# mainboard.net
KiCad netlist of a schematic drawn in EAGLE
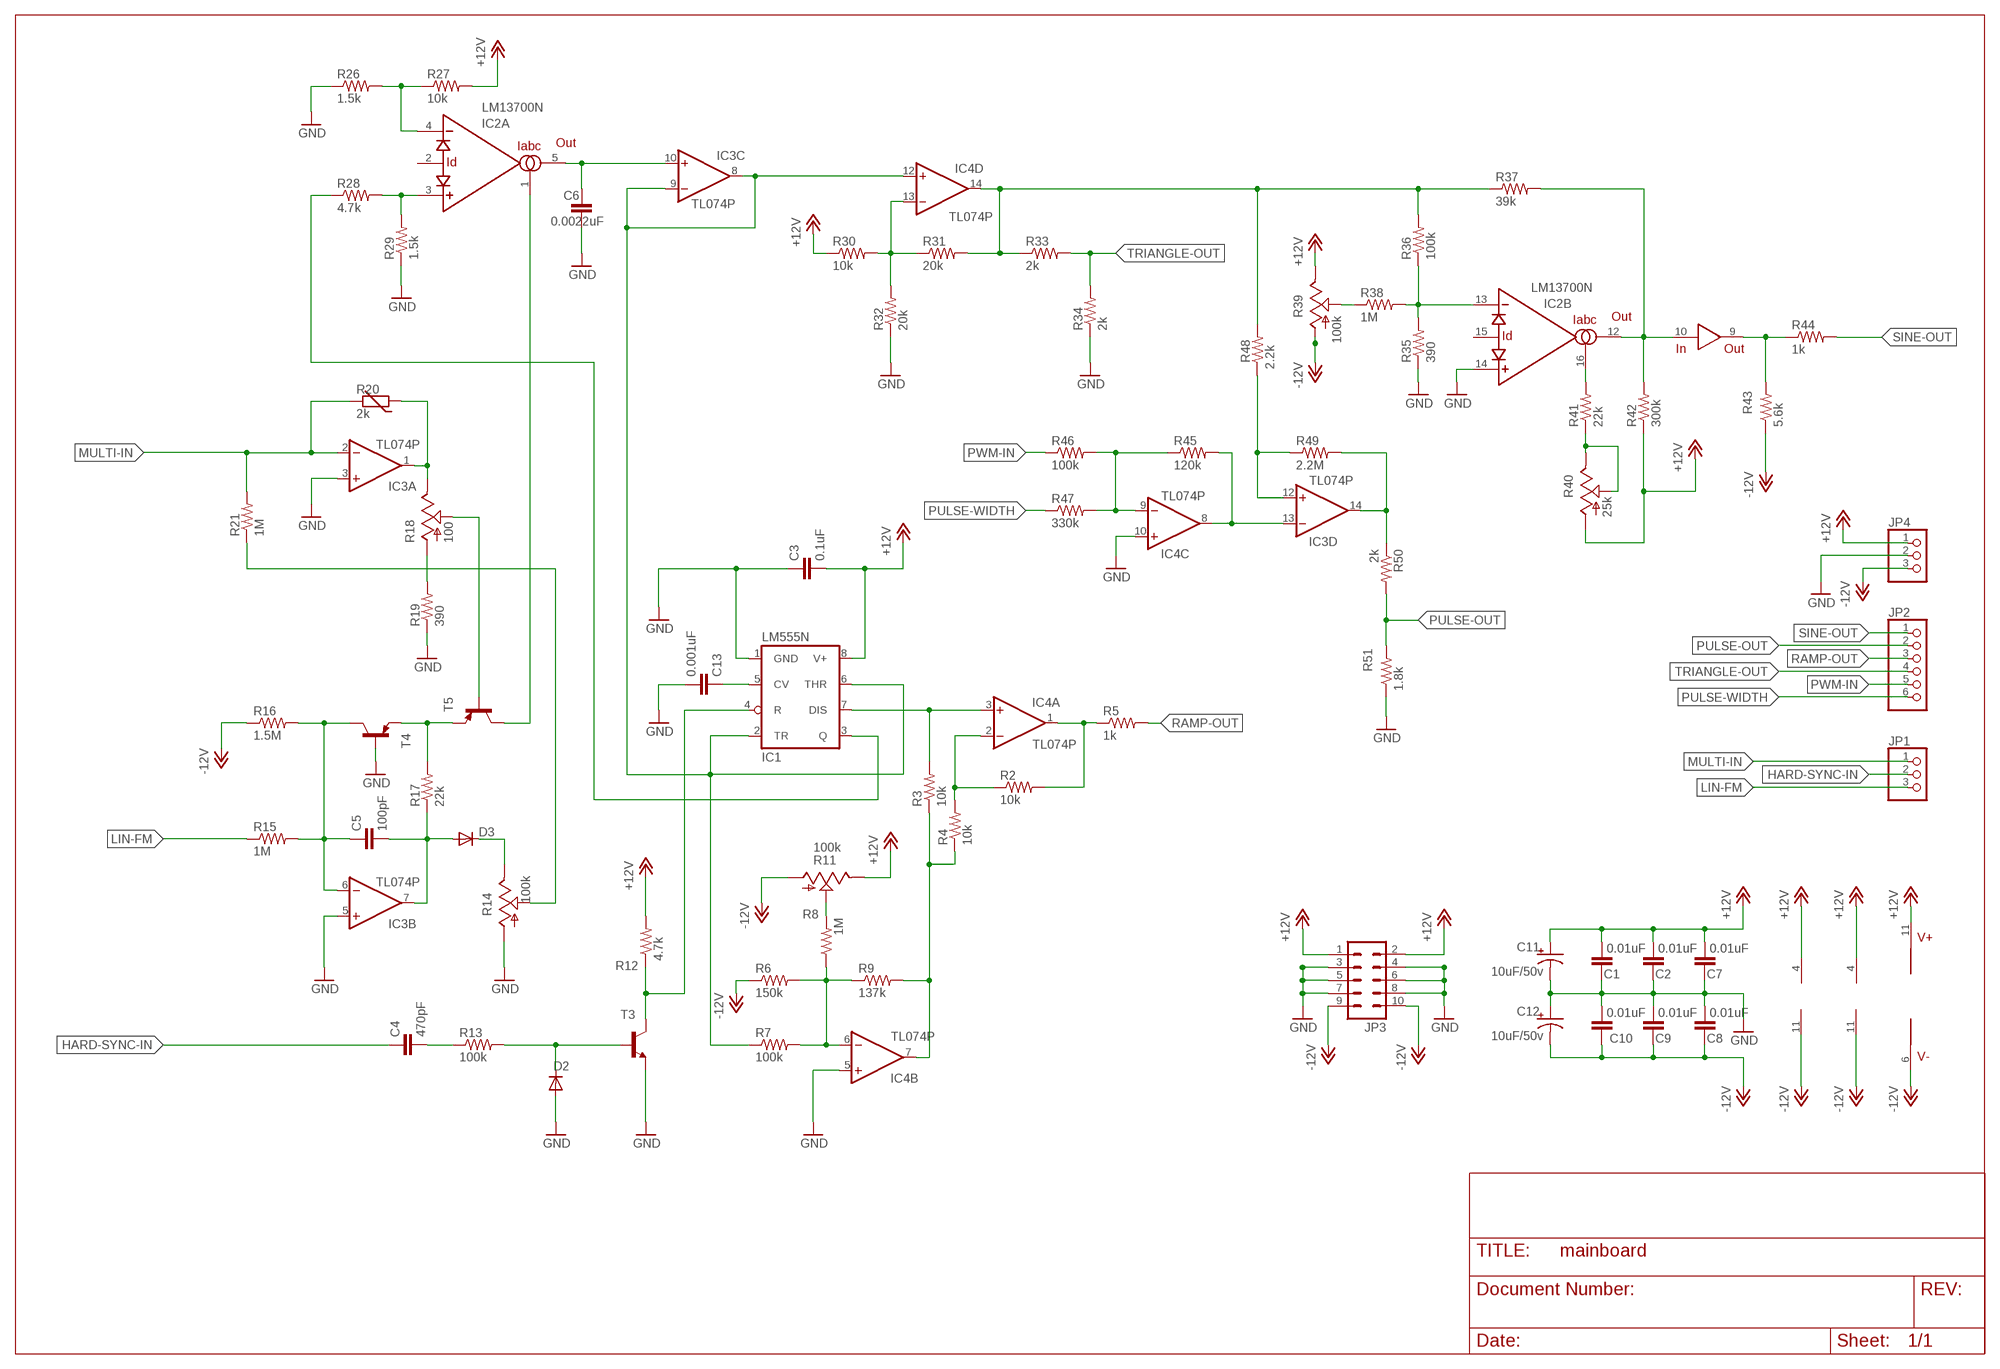
[diagram p0: schematic, sheet 1]

(export (version "E")
  (design (tool "Eeschema 10.0.6"))
  (components
    (comp (ref "C1")
      (value "0.01uF")
      (footprint "eagle-import:C050-024X044")
      (libsource (lib "eagle-import") (part "C-EU050-024X044"))
    )
    (comp (ref "C2")
      (value "0.01uF")
      (footprint "eagle-import:C050-024X044")
      (libsource (lib "eagle-import") (part "C-EU050-024X044"))
    )
    (comp (ref "C3")
      (value "0.1uF")
      (footprint "eagle-import:C050-024X044")
      (libsource (lib "eagle-import") (part "C-EU050-024X044"))
    )
    (comp (ref "C4")
      (value "470pF")
      (footprint "eagle-import:C050-024X044")
      (libsource (lib "eagle-import") (part "C-EU050-024X044"))
    )
    (comp (ref "C5")
      (value "100pF")
      (footprint "eagle-import:C050-024X044")
      (libsource (lib "eagle-import") (part "C-EU050-024X044"))
    )
    (comp (ref "C6")
      (value "0.0022uF")
      (footprint "eagle-import:C050-025X075")
      (libsource (lib "eagle-import") (part "C-EU050-025X075"))
    )
    (comp (ref "C7")
      (value "0.01uF")
      (footprint "eagle-import:C050-024X044")
      (libsource (lib "eagle-import") (part "C-EU050-024X044"))
    )
    (comp (ref "C8")
      (value "0.01uF")
      (footprint "eagle-import:C050-024X044")
      (libsource (lib "eagle-import") (part "C-EU050-024X044"))
    )
    (comp (ref "C9")
      (value "0.01uF")
      (footprint "eagle-import:C050-024X044")
      (libsource (lib "eagle-import") (part "C-EU050-024X044"))
    )
    (comp (ref "C10")
      (value "0.01uF")
      (footprint "eagle-import:C050-024X044")
      (libsource (lib "eagle-import") (part "C-EU050-024X044"))
    )
    (comp (ref "C11")
      (value "10uF/50v")
      (footprint "eagle-import:E2,5-6")
      (libsource (lib "eagle-import") (part "CPOL-USE2.5-6"))
    )
    (comp (ref "C12")
      (value "10uF/50v")
      (footprint "eagle-import:E2,5-6")
      (libsource (lib "eagle-import") (part "CPOL-USE2.5-6"))
    )
    (comp (ref "C13")
      (value "0.001uF")
      (footprint "eagle-import:C050-024X044")
      (libsource (lib "eagle-import") (part "C-EU050-024X044"))
    )
    (comp (ref "D2")
      (value "1N4148DO35-7")
      (footprint "eagle-import:DO35-7")
      (libsource (lib "eagle-import") (part "1N4148DO35-7"))
    )
    (comp (ref "D3")
      (value "1N4148DO35-7")
      (footprint "eagle-import:DO35-7")
      (libsource (lib "eagle-import") (part "1N4148DO35-7"))
    )
    (comp (ref "IC1")
      (value "LM555N")
      (footprint "eagle-import:DIL08")
      (libsource (lib "eagle-import") (part "555NLM"))
    )
    (comp (ref "IC2")
      (value "LM13700N")
      (footprint "eagle-import:DIL16")
      (libsource (lib "eagle-import") (part "LM13700N"))
    )
    (comp (ref "IC3")
      (value "TL074P")
      (footprint "eagle-import:DIL14")
      (libsource (lib "eagle-import") (part "TL074P"))
    )
    (comp (ref "IC4")
      (value "TL074P")
      (footprint "eagle-import:DIL14")
      (libsource (lib "eagle-import") (part "TL074P"))
    )
    (comp (ref "JP1")
      (value "PINHD-1X3")
      (footprint "eagle-import:1X03")
      (libsource (lib "eagle-import") (part "PINHD-1X3"))
    )
    (comp (ref "JP2")
      (value "PINHD-1X6")
      (footprint "eagle-import:1X06")
      (libsource (lib "eagle-import") (part "PINHD-1X6"))
    )
    (comp (ref "JP3")
      (value "ML10")
      (footprint "eagle-import:ML10")
      (libsource (lib "eagle-import") (part "ML10"))
    )
    (comp (ref "JP4")
      (value "PINHD-1X3")
      (footprint "eagle-import:1X03")
      (libsource (lib "eagle-import") (part "PINHD-1X3"))
    )
    (comp (ref "R2")
      (value "10k")
      (footprint "eagle-import:0204_7")
      (libsource (lib "eagle-import") (part "R-US_0204/7"))
    )
    (comp (ref "R3")
      (value "10k")
      (footprint "eagle-import:0204_7")
      (libsource (lib "eagle-import") (part "R-US_0204/7"))
    )
    (comp (ref "R4")
      (value "10k")
      (footprint "eagle-import:0204_7")
      (libsource (lib "eagle-import") (part "R-US_0204/7"))
    )
    (comp (ref "R5")
      (value "1k")
      (footprint "eagle-import:0204_7")
      (libsource (lib "eagle-import") (part "R-US_0204/7"))
    )
    (comp (ref "R6")
      (value "150k")
      (footprint "eagle-import:0204_7")
      (libsource (lib "eagle-import") (part "R-US_0204/7"))
    )
    (comp (ref "R7")
      (value "100k")
      (footprint "eagle-import:0204_7")
      (libsource (lib "eagle-import") (part "R-US_0204/7"))
    )
    (comp (ref "R8")
      (value "1M")
      (footprint "eagle-import:0204_7")
      (libsource (lib "eagle-import") (part "R-US_0204/7"))
    )
    (comp (ref "R9")
      (value "137k")
      (footprint "eagle-import:0204_7")
      (libsource (lib "eagle-import") (part "R-US_0204/7"))
    )
    (comp (ref "R11")
      (value "100k")
      (footprint "eagle-import:RJ9W")
      (libsource (lib "eagle-import") (part "TRIM_US-RJ9W"))
    )
    (comp (ref "R12")
      (value "4.7k")
      (footprint "eagle-import:0204_7")
      (libsource (lib "eagle-import") (part "R-US_0204/7"))
    )
    (comp (ref "R13")
      (value "100k")
      (footprint "eagle-import:0204_7")
      (libsource (lib "eagle-import") (part "R-US_0204/7"))
    )
    (comp (ref "R14")
      (value "100k")
      (footprint "eagle-import:RJ9W")
      (libsource (lib "eagle-import") (part "TRIM_US-RJ9W"))
    )
    (comp (ref "R15")
      (value "1M")
      (footprint "eagle-import:0204_7")
      (libsource (lib "eagle-import") (part "R-US_0204/7"))
    )
    (comp (ref "R16")
      (value "1.5M")
      (footprint "eagle-import:0204_7")
      (libsource (lib "eagle-import") (part "R-US_0204/7"))
    )
    (comp (ref "R17")
      (value "22k")
      (footprint "eagle-import:0204_7")
      (libsource (lib "eagle-import") (part "R-US_0204/7"))
    )
    (comp (ref "R18")
      (value "100")
      (footprint "eagle-import:RJ9W")
      (libsource (lib "eagle-import") (part "TRIM_US-RJ9W"))
    )
    (comp (ref "R19")
      (value "390")
      (footprint "eagle-import:0204_7")
      (libsource (lib "eagle-import") (part "R-US_0204/7"))
    )
    (comp (ref "R20")
      (value "2k")
      (footprint "eagle-import:R-5")
      (libsource (lib "eagle-import") (part "THERMISTOR-5"))
    )
    (comp (ref "R21")
      (value "1M")
      (footprint "eagle-import:0204_7")
      (libsource (lib "eagle-import") (part "R-US_0204/7"))
    )
    (comp (ref "R26")
      (value "1.5k")
      (footprint "eagle-import:0204_7")
      (libsource (lib "eagle-import") (part "R-US_0204/7"))
    )
    (comp (ref "R27")
      (value "10k")
      (footprint "eagle-import:0204_7")
      (libsource (lib "eagle-import") (part "R-US_0204/7"))
    )
    (comp (ref "R28")
      (value "4.7k")
      (footprint "eagle-import:0204_7")
      (libsource (lib "eagle-import") (part "R-US_0204/7"))
    )
    (comp (ref "R29")
      (value "1.5k")
      (footprint "eagle-import:0204_7")
      (libsource (lib "eagle-import") (part "R-US_0204/7"))
    )
    (comp (ref "R30")
      (value "10k")
      (footprint "eagle-import:0204_7")
      (libsource (lib "eagle-import") (part "R-US_0204/7"))
    )
    (comp (ref "R31")
      (value "20k")
      (footprint "eagle-import:0204_7")
      (libsource (lib "eagle-import") (part "R-US_0204/7"))
    )
    (comp (ref "R32")
      (value "20k")
      (footprint "eagle-import:0204_7")
      (libsource (lib "eagle-import") (part "R-US_0204/7"))
    )
    (comp (ref "R33")
      (value "2k")
      (footprint "eagle-import:0204_7")
      (libsource (lib "eagle-import") (part "R-US_0204/7"))
    )
    (comp (ref "R34")
      (value "2k")
      (footprint "eagle-import:0204_7")
      (libsource (lib "eagle-import") (part "R-US_0204/7"))
    )
    (comp (ref "R35")
      (value "390")
      (footprint "eagle-import:0204_7")
      (libsource (lib "eagle-import") (part "R-US_0204/7"))
    )
    (comp (ref "R36")
      (value "100k")
      (footprint "eagle-import:0204_7")
      (libsource (lib "eagle-import") (part "R-US_0204/7"))
    )
    (comp (ref "R37")
      (value "39k")
      (footprint "eagle-import:0204_7")
      (libsource (lib "eagle-import") (part "R-US_0204/7"))
    )
    (comp (ref "R38")
      (value "1M")
      (footprint "eagle-import:0204_7")
      (libsource (lib "eagle-import") (part "R-US_0204/7"))
    )
    (comp (ref "R39")
      (value "100k")
      (footprint "eagle-import:RJ9W")
      (libsource (lib "eagle-import") (part "TRIM_US-RJ9W"))
    )
    (comp (ref "R40")
      (value "25k")
      (footprint "eagle-import:RJ9W")
      (libsource (lib "eagle-import") (part "TRIM_US-RJ9W"))
    )
    (comp (ref "R41")
      (value "22k")
      (footprint "eagle-import:0204_7")
      (libsource (lib "eagle-import") (part "R-US_0204/7"))
    )
    (comp (ref "R42")
      (value "300k")
      (footprint "eagle-import:0204_7")
      (libsource (lib "eagle-import") (part "R-US_0204/7"))
    )
    (comp (ref "R43")
      (value "5.6k")
      (footprint "eagle-import:0204_7")
      (libsource (lib "eagle-import") (part "R-US_0204/7"))
    )
    (comp (ref "R44")
      (value "1k")
      (footprint "eagle-import:0204_7")
      (libsource (lib "eagle-import") (part "R-US_0204/7"))
    )
    (comp (ref "R45")
      (value "120k")
      (footprint "eagle-import:0204_7")
      (libsource (lib "eagle-import") (part "R-US_0204/7"))
    )
    (comp (ref "R46")
      (value "100k")
      (footprint "eagle-import:0204_7")
      (libsource (lib "eagle-import") (part "R-US_0204/7"))
    )
    (comp (ref "R47")
      (value "330k")
      (footprint "eagle-import:0204_7")
      (libsource (lib "eagle-import") (part "R-US_0204/7"))
    )
    (comp (ref "R48")
      (value "2.2k")
      (footprint "eagle-import:0204_7")
      (libsource (lib "eagle-import") (part "R-US_0204/7"))
    )
    (comp (ref "R49")
      (value "2.2M")
      (footprint "eagle-import:0204_7")
      (libsource (lib "eagle-import") (part "R-US_0204/7"))
    )
    (comp (ref "R50")
      (value "2k")
      (footprint "eagle-import:0204_7")
      (libsource (lib "eagle-import") (part "R-US_0204/7"))
    )
    (comp (ref "R51")
      (value "1.8k")
      (footprint "eagle-import:0204_7")
      (libsource (lib "eagle-import") (part "R-US_0204/7"))
    )
    (comp (ref "T3")
      (value "2N3904-NPN-TO92-EBC")
      (footprint "eagle-import:TO92-EBC")
      (libsource (lib "eagle-import") (part "-NPN-TO92-EBC2N3904"))
    )
    (comp (ref "T4")
      (value "2N3906-PNP-TO92-EBC")
      (footprint "eagle-import:TO92-EBC")
      (libsource (lib "eagle-import") (part "-PNP-TO92-EBC2N3906"))
    )
    (comp (ref "T5")
      (value "2N3906-PNP-TO92-EBC")
      (footprint "eagle-import:TO92-EBC")
      (libsource (lib "eagle-import") (part "-PNP-TO92-EBC2N3906"))
    )
  )
  (nets
    (net (code "1") (name "+12V") (class "Default")
      (node (ref "C1") (pin "2") (pinfunction "2_2") (pintype "passive"))
      (node (ref "C11") (pin "+") (pinfunction "+_+") (pintype "passive"))
      (node (ref "C2") (pin "2") (pinfunction "2_2") (pintype "passive"))
      (node (ref "C3") (pin "2") (pinfunction "2_2") (pintype "passive"))
      (node (ref "C7") (pin "2") (pinfunction "2_2") (pintype "passive"))
      (node (ref "IC1") (pin "8") (pinfunction "V+_8") (pintype "power_in"))
      (node (ref "IC2") (pin "11") (pinfunction "V+_11") (pintype "bidirectional"))
      (node (ref "IC3") (pin "4") (pinfunction "V+_4") (pintype "power_in"))
      (node (ref "IC4") (pin "4") (pinfunction "V+_4") (pintype "power_in"))
      (node (ref "JP3") (pin "1") (pinfunction "1_1") (pintype "passive"))
      (node (ref "JP3") (pin "2") (pinfunction "2_2") (pintype "passive"))
      (node (ref "JP4") (pin "1") (pinfunction "1_1") (pintype "passive"))
      (node (ref "R11") (pin "E") (pinfunction "E_E") (pintype "passive"))
      (node (ref "R12") (pin "2") (pinfunction "2_2") (pintype "passive"))
      (node (ref "R27") (pin "2") (pinfunction "2_2") (pintype "passive"))
      (node (ref "R30") (pin "1") (pinfunction "1_1") (pintype "passive"))
      (node (ref "R39") (pin "E") (pinfunction "E_E") (pintype "passive"))
      (node (ref "R40") (pin "A") (pinfunction "A_A") (pintype "passive"))
      (node (ref "R42") (pin "1") (pinfunction "1_1") (pintype "passive"))
    )
    (net (code "2") (name "-12V") (class "Default")
      (node (ref "C10") (pin "1") (pinfunction "1_1") (pintype "passive"))
      (node (ref "C12") (pin "-") (pinfunction "-_-") (pintype "passive"))
      (node (ref "C8") (pin "1") (pinfunction "1_1") (pintype "passive"))
      (node (ref "C9") (pin "1") (pinfunction "1_1") (pintype "passive"))
      (node (ref "IC2") (pin "6") (pinfunction "V-_6") (pintype "bidirectional"))
      (node (ref "IC3") (pin "11") (pinfunction "V-_11") (pintype "power_in"))
      (node (ref "IC4") (pin "11") (pinfunction "V-_11") (pintype "power_in"))
      (node (ref "JP3") (pin "10") (pinfunction "10_10") (pintype "passive"))
      (node (ref "JP3") (pin "9") (pinfunction "9_9") (pintype "passive"))
      (node (ref "JP4") (pin "3") (pinfunction "3_3") (pintype "passive"))
      (node (ref "R11") (pin "A") (pinfunction "A_A") (pintype "passive"))
      (node (ref "R16") (pin "1") (pinfunction "1_1") (pintype "passive"))
      (node (ref "R39") (pin "A") (pinfunction "A_A") (pintype "passive"))
      (node (ref "R43") (pin "1") (pinfunction "1_1") (pintype "passive"))
      (node (ref "R6") (pin "1") (pinfunction "1_1") (pintype "passive"))
    )
    (net (code "3") (name "GND") (class "Default")
      (node (ref "C1") (pin "1") (pinfunction "1_1") (pintype "passive"))
      (node (ref "C10") (pin "2") (pinfunction "2_2") (pintype "passive"))
      (node (ref "C11") (pin "-") (pinfunction "-_-") (pintype "passive"))
      (node (ref "C12") (pin "+") (pinfunction "+_+") (pintype "passive"))
      (node (ref "C13") (pin "1") (pinfunction "1_1") (pintype "passive"))
      (node (ref "C2") (pin "1") (pinfunction "1_1") (pintype "passive"))
      (node (ref "C3") (pin "1") (pinfunction "1_1") (pintype "passive"))
      (node (ref "C6") (pin "2") (pinfunction "2_2") (pintype "passive"))
      (node (ref "C7") (pin "1") (pinfunction "1_1") (pintype "passive"))
      (node (ref "C8") (pin "2") (pinfunction "2_2") (pintype "passive"))
      (node (ref "C9") (pin "2") (pinfunction "2_2") (pintype "passive"))
      (node (ref "D2") (pin "A") (pinfunction "A_A") (pintype "passive"))
      (node (ref "IC1") (pin "1") (pinfunction "GND_1") (pintype "power_in"))
      (node (ref "IC2") (pin "14") (pinfunction "+IN_14") (pintype "bidirectional"))
      (node (ref "IC3") (pin "3") (pinfunction "+IN_3") (pintype "input"))
      (node (ref "IC3") (pin "5") (pinfunction "+IN_5") (pintype "input"))
      (node (ref "IC4") (pin "10") (pinfunction "+IN_10") (pintype "input"))
      (node (ref "IC4") (pin "5") (pinfunction "+IN_5") (pintype "input"))
      (node (ref "JP3") (pin "3") (pinfunction "3_3") (pintype "passive"))
      (node (ref "JP3") (pin "4") (pinfunction "4_4") (pintype "passive"))
      (node (ref "JP3") (pin "5") (pinfunction "5_5") (pintype "passive"))
      (node (ref "JP3") (pin "6") (pinfunction "6_6") (pintype "passive"))
      (node (ref "JP3") (pin "7") (pinfunction "7_7") (pintype "passive"))
      (node (ref "JP3") (pin "8") (pinfunction "8_8") (pintype "passive"))
      (node (ref "JP4") (pin "2") (pinfunction "2_2") (pintype "passive"))
      (node (ref "R14") (pin "A") (pinfunction "A_A") (pintype "passive"))
      (node (ref "R19") (pin "1") (pinfunction "1_1") (pintype "passive"))
      (node (ref "R26") (pin "1") (pinfunction "1_1") (pintype "passive"))
      (node (ref "R29") (pin "1") (pinfunction "1_1") (pintype "passive"))
      (node (ref "R32") (pin "1") (pinfunction "1_1") (pintype "passive"))
      (node (ref "R34") (pin "1") (pinfunction "1_1") (pintype "passive"))
      (node (ref "R35") (pin "1") (pinfunction "1_1") (pintype "passive"))
      (node (ref "R51") (pin "1") (pinfunction "1_1") (pintype "passive"))
      (node (ref "T3") (pin "E") (pinfunction "E_E") (pintype "passive"))
      (node (ref "T4") (pin "B") (pinfunction "B_B") (pintype "passive"))
    )
    (net (code "4") (name "HARD-SYNC-IN") (class "Default")
      (node (ref "C4") (pin "1") (pinfunction "1_1") (pintype "passive"))
      (node (ref "JP1") (pin "2") (pinfunction "2_2") (pintype "passive"))
    )
    (net (code "5") (name "LIN-FM") (class "Default")
      (node (ref "JP1") (pin "3") (pinfunction "3_3") (pintype "passive"))
      (node (ref "R15") (pin "1") (pinfunction "1_1") (pintype "passive"))
    )
    (net (code "6") (name "MULTI-IN") (class "Default")
      (node (ref "IC3") (pin "2") (pinfunction "-IN_2") (pintype "input"))
      (node (ref "JP1") (pin "1") (pinfunction "1_1") (pintype "passive"))
      (node (ref "R20") (pin "2") (pinfunction "2_2") (pintype "passive"))
      (node (ref "R21") (pin "2") (pinfunction "2_2") (pintype "passive"))
    )
    (net (code "7") (name "Net-(C4-Pad2)") (class "Default")
      (node (ref "C4") (pin "2") (pinfunction "2_2") (pintype "passive"))
      (node (ref "R13") (pin "1") (pinfunction "1_1") (pintype "passive"))
    )
    (net (code "8") (name "Net-(D2-PadC)") (class "Default")
      (node (ref "D2") (pin "C") (pinfunction "C_C") (pintype "passive"))
      (node (ref "R13") (pin "2") (pinfunction "2_2") (pintype "passive"))
      (node (ref "T3") (pin "B") (pinfunction "B_B") (pintype "passive"))
    )
    (net (code "9") (name "Net-(D3-PadC)") (class "Default")
      (node (ref "D3") (pin "C") (pinfunction "C_C") (pintype "passive"))
      (node (ref "R14") (pin "E") (pinfunction "E_E") (pintype "passive"))
    )
    (net (code "10") (name "Net-(IC1-CV)") (class "Default")
      (node (ref "C13") (pin "2") (pinfunction "2_2") (pintype "passive"))
      (node (ref "IC1") (pin "5") (pinfunction "CV_5") (pintype "input"))
    )
    (net (code "11") (name "Net-(IC1-DIS)") (class "Default")
      (node (ref "IC1") (pin "7") (pinfunction "DIS_7") (pintype "input"))
      (node (ref "IC4") (pin "3") (pinfunction "+IN_3") (pintype "input"))
      (node (ref "R3") (pin "2") (pinfunction "2_2") (pintype "passive"))
    )
    (net (code "12") (name "Net-(IC1-Q)") (class "Default")
      (node (ref "IC1") (pin "3") (pinfunction "Q_3") (pintype "output"))
      (node (ref "R28") (pin "1") (pinfunction "1_1") (pintype "passive"))
    )
    (net (code "13") (name "Net-(IC1-R)") (class "Default")
      (node (ref "IC1") (pin "4") (pinfunction "R_4") (pintype "input"))
      (node (ref "R12") (pin "1") (pinfunction "1_1") (pintype "passive"))
      (node (ref "T3") (pin "C") (pinfunction "C_C") (pintype "passive"))
    )
    (net (code "14") (name "Net-(IC1-THR)") (class "Default")
      (node (ref "IC1") (pin "2") (pinfunction "TR_2") (pintype "input"))
      (node (ref "IC1") (pin "6") (pinfunction "THR_6") (pintype "input"))
      (node (ref "IC3") (pin "8") (pinfunction "OUT_8") (pintype "output"))
      (node (ref "IC3") (pin "9") (pinfunction "-IN_9") (pintype "input"))
      (node (ref "IC4") (pin "12") (pinfunction "+IN_12") (pintype "input"))
      (node (ref "R7") (pin "1") (pinfunction "1_1") (pintype "passive"))
    )
    (net (code "15") (name "Net-(IC2A-+IN)") (class "Default")
      (node (ref "IC2") (pin "3") (pinfunction "+IN_3") (pintype "bidirectional"))
      (node (ref "R28") (pin "2") (pinfunction "2_2") (pintype "passive"))
      (node (ref "R29") (pin "2") (pinfunction "2_2") (pintype "passive"))
    )
    (net (code "16") (name "Net-(IC2A--IN)") (class "Default")
      (node (ref "IC2") (pin "4") (pinfunction "-IN_4") (pintype "bidirectional"))
      (node (ref "R26") (pin "2") (pinfunction "2_2") (pintype "passive"))
      (node (ref "R27") (pin "1") (pinfunction "1_1") (pintype "passive"))
    )
    (net (code "17") (name "Net-(IC2A-IABC)") (class "Default")
      (node (ref "IC2") (pin "1") (pinfunction "IABC_1") (pintype "bidirectional"))
      (node (ref "T5") (pin "C") (pinfunction "C_C") (pintype "passive"))
    )
    (net (code "18") (name "Net-(IC2A-OUT)") (class "Default")
      (node (ref "C6") (pin "1") (pinfunction "1_1") (pintype "passive"))
      (node (ref "IC2") (pin "5") (pinfunction "OUT_5") (pintype "bidirectional"))
      (node (ref "IC3") (pin "10") (pinfunction "+IN_10") (pintype "input"))
    )
    (net (code "19") (name "Net-(IC2B--IN)") (class "Default")
      (node (ref "IC2") (pin "13") (pinfunction "-IN_13") (pintype "bidirectional"))
      (node (ref "R35") (pin "2") (pinfunction "2_2") (pintype "passive"))
      (node (ref "R36") (pin "1") (pinfunction "1_1") (pintype "passive"))
      (node (ref "R38") (pin "2") (pinfunction "2_2") (pintype "passive"))
    )
    (net (code "20") (name "Net-(IC2B-IABC)") (class "Default")
      (node (ref "IC2") (pin "16") (pinfunction "IABC_16") (pintype "bidirectional"))
      (node (ref "R41") (pin "2") (pinfunction "2_2") (pintype "passive"))
    )
    (net (code "21") (name "Net-(IC2B-OUT)") (class "Default")
      (node (ref "IC2") (pin "10") (pinfunction "IN_10") (pintype "bidirectional"))
      (node (ref "IC2") (pin "12") (pinfunction "OUT_12") (pintype "bidirectional"))
      (node (ref "R37") (pin "2") (pinfunction "2_2") (pintype "passive"))
      (node (ref "R42") (pin "2") (pinfunction "2_2") (pintype "passive"))
    )
    (net (code "22") (name "Net-(IC2D-OUT)") (class "Default")
      (node (ref "IC2") (pin "9") (pinfunction "OUT_9") (pintype "bidirectional"))
      (node (ref "R43") (pin "2") (pinfunction "2_2") (pintype "passive"))
      (node (ref "R44") (pin "1") (pinfunction "1_1") (pintype "passive"))
    )
    (net (code "23") (name "Net-(IC3A-OUT)") (class "Default")
      (node (ref "IC3") (pin "1") (pinfunction "OUT_1") (pintype "output"))
      (node (ref "R18") (pin "E") (pinfunction "E_E") (pintype "passive"))
      (node (ref "R20") (pin "1") (pinfunction "1_1") (pintype "passive"))
    )
    (net (code "24") (name "Net-(IC3B--IN)") (class "Default")
      (node (ref "C5") (pin "1") (pinfunction "1_1") (pintype "passive"))
      (node (ref "IC3") (pin "6") (pinfunction "-IN_6") (pintype "input"))
      (node (ref "R15") (pin "2") (pinfunction "2_2") (pintype "passive"))
      (node (ref "R16") (pin "2") (pinfunction "2_2") (pintype "passive"))
      (node (ref "T4") (pin "C") (pinfunction "C_C") (pintype "passive"))
    )
    (net (code "25") (name "Net-(IC3B-OUT)") (class "Default")
      (node (ref "C5") (pin "2") (pinfunction "2_2") (pintype "passive"))
      (node (ref "D3") (pin "A") (pinfunction "A_A") (pintype "passive"))
      (node (ref "IC3") (pin "7") (pinfunction "OUT_7") (pintype "output"))
      (node (ref "R17") (pin "1") (pinfunction "1_1") (pintype "passive"))
    )
    (net (code "26") (name "Net-(IC3D-+IN)") (class "Default")
      (node (ref "IC3") (pin "12") (pinfunction "+IN_12") (pintype "input"))
      (node (ref "R48") (pin "1") (pinfunction "1_1") (pintype "passive"))
      (node (ref "R49") (pin "1") (pinfunction "1_1") (pintype "passive"))
    )
    (net (code "27") (name "Net-(IC3D--IN)") (class "Default")
      (node (ref "IC3") (pin "13") (pinfunction "-IN_13") (pintype "input"))
      (node (ref "IC4") (pin "8") (pinfunction "OUT_8") (pintype "output"))
      (node (ref "R45") (pin "2") (pinfunction "2_2") (pintype "passive"))
    )
    (net (code "28") (name "Net-(IC3D-OUT)") (class "Default")
      (node (ref "IC3") (pin "14") (pinfunction "OUT_14") (pintype "output"))
      (node (ref "R49") (pin "2") (pinfunction "2_2") (pintype "passive"))
      (node (ref "R50") (pin "1") (pinfunction "1_1") (pintype "passive"))
    )
    (net (code "29") (name "Net-(IC4A--IN)") (class "Default")
      (node (ref "IC4") (pin "2") (pinfunction "-IN_2") (pintype "input"))
      (node (ref "R2") (pin "1") (pinfunction "1_1") (pintype "passive"))
      (node (ref "R4") (pin "2") (pinfunction "2_2") (pintype "passive"))
    )
    (net (code "30") (name "Net-(IC4A-OUT)") (class "Default")
      (node (ref "IC4") (pin "1") (pinfunction "OUT_1") (pintype "output"))
      (node (ref "R2") (pin "2") (pinfunction "2_2") (pintype "passive"))
      (node (ref "R5") (pin "1") (pinfunction "1_1") (pintype "passive"))
    )
    (net (code "31") (name "Net-(IC4B--IN)") (class "Default")
      (node (ref "IC4") (pin "6") (pinfunction "-IN_6") (pintype "input"))
      (node (ref "R6") (pin "2") (pinfunction "2_2") (pintype "passive"))
      (node (ref "R7") (pin "2") (pinfunction "2_2") (pintype "passive"))
      (node (ref "R8") (pin "1") (pinfunction "1_1") (pintype "passive"))
      (node (ref "R9") (pin "1") (pinfunction "1_1") (pintype "passive"))
    )
    (net (code "32") (name "Net-(IC4B-OUT)") (class "Default")
      (node (ref "IC4") (pin "7") (pinfunction "OUT_7") (pintype "output"))
      (node (ref "R3") (pin "1") (pinfunction "1_1") (pintype "passive"))
      (node (ref "R4") (pin "1") (pinfunction "1_1") (pintype "passive"))
      (node (ref "R9") (pin "2") (pinfunction "2_2") (pintype "passive"))
    )
    (net (code "33") (name "Net-(IC4C--IN)") (class "Default")
      (node (ref "IC4") (pin "9") (pinfunction "-IN_9") (pintype "input"))
      (node (ref "R45") (pin "1") (pinfunction "1_1") (pintype "passive"))
      (node (ref "R46") (pin "2") (pinfunction "2_2") (pintype "passive"))
      (node (ref "R47") (pin "2") (pinfunction "2_2") (pintype "passive"))
    )
    (net (code "34") (name "Net-(IC4D--IN)") (class "Default")
      (node (ref "IC4") (pin "13") (pinfunction "-IN_13") (pintype "input"))
      (node (ref "R30") (pin "2") (pinfunction "2_2") (pintype "passive"))
      (node (ref "R31") (pin "1") (pinfunction "1_1") (pintype "passive"))
      (node (ref "R32") (pin "2") (pinfunction "2_2") (pintype "passive"))
    )
    (net (code "35") (name "Net-(IC4D-OUT)") (class "Default")
      (node (ref "IC4") (pin "14") (pinfunction "OUT_14") (pintype "output"))
      (node (ref "R31") (pin "2") (pinfunction "2_2") (pintype "passive"))
      (node (ref "R33") (pin "1") (pinfunction "1_1") (pintype "passive"))
      (node (ref "R36") (pin "2") (pinfunction "2_2") (pintype "passive"))
      (node (ref "R37") (pin "1") (pinfunction "1_1") (pintype "passive"))
      (node (ref "R48") (pin "2") (pinfunction "2_2") (pintype "passive"))
    )
    (net (code "36") (name "Net-(R11-PadS)") (class "Default")
      (node (ref "R11") (pin "S") (pinfunction "S_S") (pintype "passive"))
      (node (ref "R8") (pin "2") (pinfunction "2_2") (pintype "passive"))
    )
    (net (code "37") (name "Net-(R14-PadS)") (class "Default")
      (node (ref "R14") (pin "S") (pinfunction "S_S") (pintype "passive"))
      (node (ref "R21") (pin "1") (pinfunction "1_1") (pintype "passive"))
    )
    (net (code "38") (name "Net-(R17-Pad2)") (class "Default")
      (node (ref "R17") (pin "2") (pinfunction "2_2") (pintype "passive"))
      (node (ref "T4") (pin "E") (pinfunction "E_E") (pintype "passive"))
      (node (ref "T5") (pin "E") (pinfunction "E_E") (pintype "passive"))
    )
    (net (code "39") (name "Net-(R18-PadA)") (class "Default")
      (node (ref "R18") (pin "A") (pinfunction "A_A") (pintype "passive"))
      (node (ref "R19") (pin "2") (pinfunction "2_2") (pintype "passive"))
    )
    (net (code "40") (name "Net-(R18-PadS)") (class "Default")
      (node (ref "R18") (pin "S") (pinfunction "S_S") (pintype "passive"))
      (node (ref "T5") (pin "B") (pinfunction "B_B") (pintype "passive"))
    )
    (net (code "41") (name "Net-(R38-Pad1)") (class "Default")
      (node (ref "R38") (pin "1") (pinfunction "1_1") (pintype "passive"))
      (node (ref "R39") (pin "S") (pinfunction "S_S") (pintype "passive"))
    )
    (net (code "42") (name "Net-(R40-PadE)") (class "Default")
      (node (ref "R40") (pin "E") (pinfunction "E_E") (pintype "passive"))
      (node (ref "R40") (pin "S") (pinfunction "S_S") (pintype "passive"))
      (node (ref "R41") (pin "1") (pinfunction "1_1") (pintype "passive"))
    )
    (net (code "43") (name "PULSE-OUT") (class "Default")
      (node (ref "JP2") (pin "2") (pinfunction "2_2") (pintype "passive"))
      (node (ref "R50") (pin "2") (pinfunction "2_2") (pintype "passive"))
      (node (ref "R51") (pin "2") (pinfunction "2_2") (pintype "passive"))
    )
    (net (code "44") (name "PULSE-WIDTH") (class "Default")
      (node (ref "JP2") (pin "6") (pinfunction "6_6") (pintype "passive"))
      (node (ref "R47") (pin "1") (pinfunction "1_1") (pintype "passive"))
    )
    (net (code "45") (name "PWM-IN") (class "Default")
      (node (ref "JP2") (pin "5") (pinfunction "5_5") (pintype "passive"))
      (node (ref "R46") (pin "1") (pinfunction "1_1") (pintype "passive"))
    )
    (net (code "46") (name "RAMP-OUT") (class "Default")
      (node (ref "JP2") (pin "3") (pinfunction "3_3") (pintype "passive"))
      (node (ref "R5") (pin "2") (pinfunction "2_2") (pintype "passive"))
    )
    (net (code "47") (name "SINE-OUT") (class "Default")
      (node (ref "JP2") (pin "1") (pinfunction "1_1") (pintype "passive"))
      (node (ref "R44") (pin "2") (pinfunction "2_2") (pintype "passive"))
    )
    (net (code "48") (name "TRIANGLE-OUT") (class "Default")
      (node (ref "JP2") (pin "4") (pinfunction "4_4") (pintype "passive"))
      (node (ref "R33") (pin "2") (pinfunction "2_2") (pintype "passive"))
      (node (ref "R34") (pin "2") (pinfunction "2_2") (pintype "passive"))
    )
    (net (code "49") (name "unconnected-(IC2A-ID-Pad2)") (class "Default")
      (node (ref "IC2") (pin "2") (pinfunction "ID_2") (pintype "bidirectional"))
    )
    (net (code "50") (name "unconnected-(IC2B-ID-Pad15)") (class "Default")
      (node (ref "IC2") (pin "15") (pinfunction "ID_15") (pintype "bidirectional"))
    )
  )
)
